# FMC_connectors.net
KiCad netlist of a schematic drawn in Altium Designer
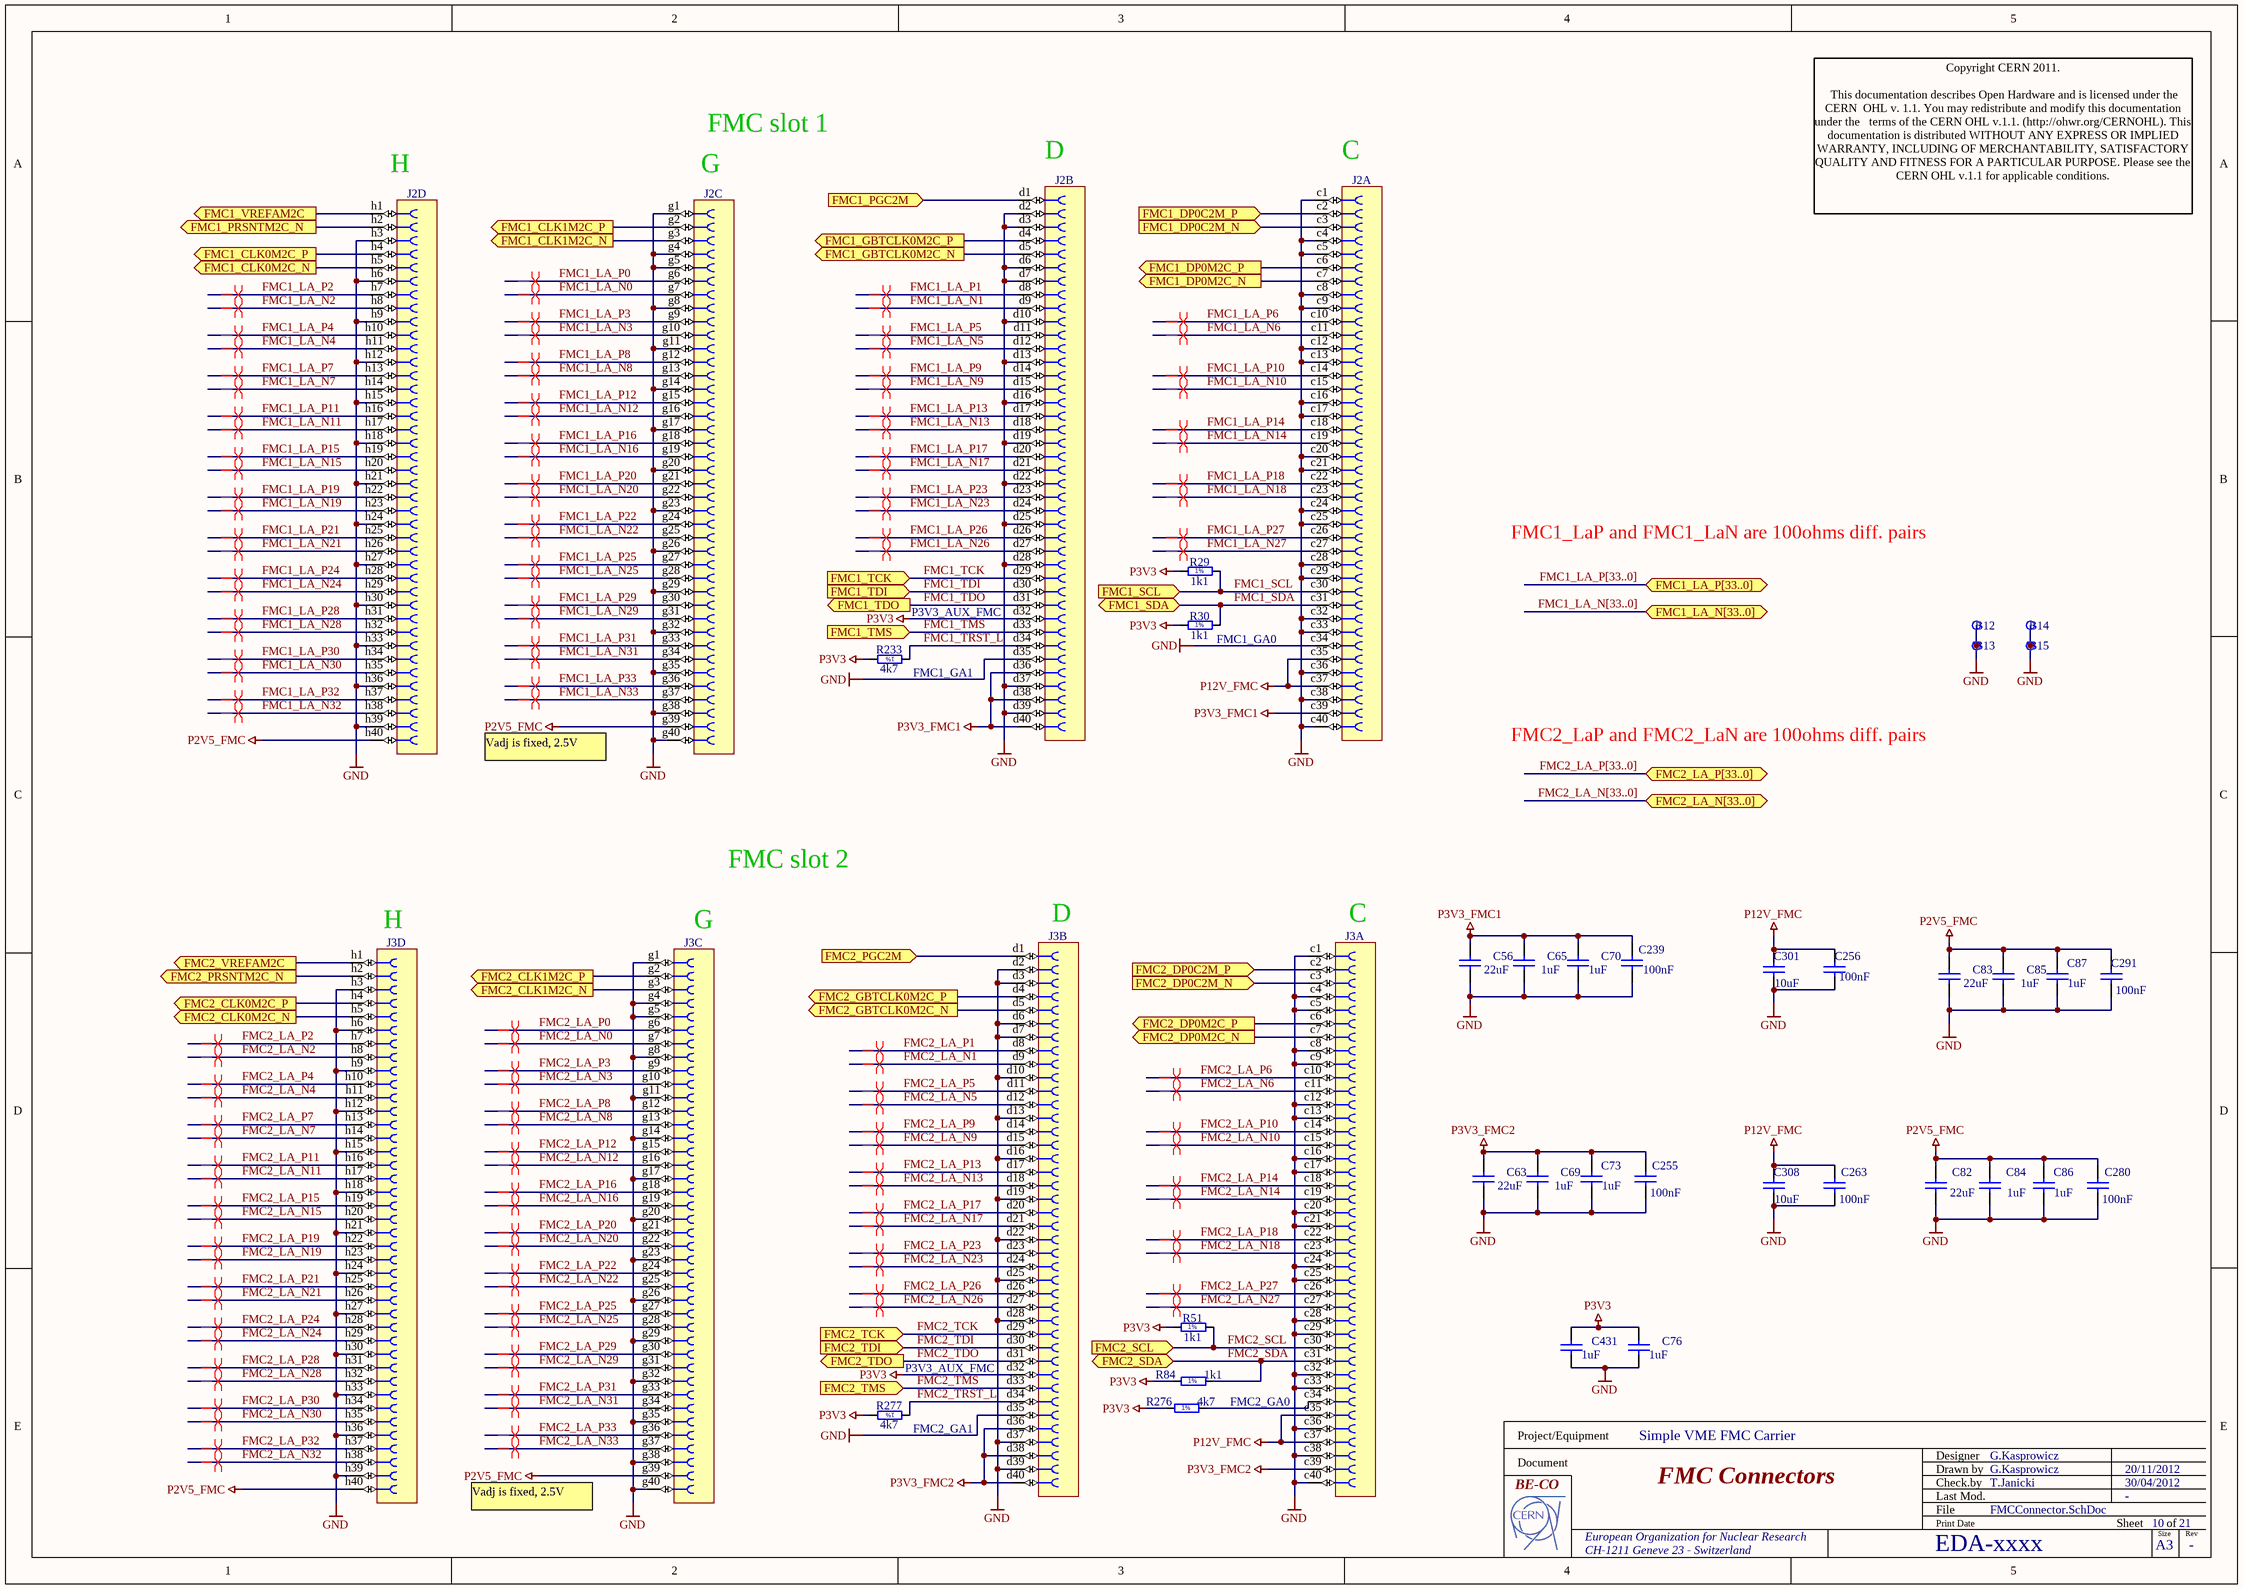
[diagram p0: FMC_connectors.SchDoc]

(export (version "E")
  (design (tool "Eeschema 10.0.6"))
  (components
    (comp (ref "B12")
      (value "Plated Hole")
      (footprint "MTG270_500")
      (description "Single Terminal Socket")
      (fields (field (name "PART NUMBER") "PLATED_HOLE2.7_PAD5.0") (field (name "AUTHOR") "CERN DEM JMW"))
      (libsource (lib "Eletro-mechanical") (part "Single Terminal Socket"))
    )
    (comp (ref "B13")
      (value "Plated Hole")
      (footprint "MTG270_500")
      (description "Single Terminal Socket")
      (fields (field (name "PART NUMBER") "PLATED_HOLE2.7_PAD5.0") (field (name "AUTHOR") "CERN DEM JMW"))
      (libsource (lib "Eletro-mechanical") (part "Single Terminal Socket"))
    )
    (comp (ref "B14")
      (value "Plated Hole")
      (footprint "MTG270_500")
      (description "Single Terminal Socket")
      (fields (field (name "PART NUMBER") "PLATED_HOLE2.7_PAD5.0") (field (name "AUTHOR") "CERN DEM JMW"))
      (libsource (lib "Eletro-mechanical") (part "Single Terminal Socket"))
    )
    (comp (ref "B15")
      (value "Plated Hole")
      (footprint "MTG270_500")
      (description "Single Terminal Socket")
      (fields (field (name "PART NUMBER") "PLATED_HOLE2.7_PAD5.0") (field (name "AUTHOR") "CERN DEM JMW"))
      (libsource (lib "Eletro-mechanical") (part "Single Terminal Socket"))
    )
    (comp (ref "C56")
      (value "22uF")
      (footprint "CAPC3216X180N")
      (description "Non-polarised capacitor")
      (fields
        (field (name "PART NUMBER") "CC1206_22UF_10V_10%_X7R")
        (field (name "VOLTAGE") "10V")
        (field (name "AUTHOR") "CERN DEM JLC")
      )
      (libsource (lib "Capacitors") (part "Capacitor - non polarized"))
    )
    (comp (ref "C63")
      (value "22uF")
      (footprint "CAPC3216X180N")
      (description "Non-polarised capacitor")
      (fields
        (field (name "PART NUMBER") "CC1206_22UF_10V_10%_X7R")
        (field (name "VOLTAGE") "10V")
        (field (name "AUTHOR") "CERN DEM JLC")
      )
      (libsource (lib "Capacitors") (part "Capacitor - non polarized"))
    )
    (comp (ref "C65")
      (value "1uF")
      (footprint "CAPC1608X87N")
      (description "Non-polarised capacitor")
      (fields
        (field (name "PART NUMBER") "CC0603_1UF_16V_10%_X7R")
        (field (name "VOLTAGE") "16V")
        (field (name "AUTHOR") "CERN DEM JLC")
      )
      (libsource (lib "Capacitors") (part "Capacitor - non polarized"))
    )
    (comp (ref "C69")
      (value "1uF")
      (footprint "CAPC1608X87N")
      (description "Non-polarised capacitor")
      (fields
        (field (name "PART NUMBER") "CC0603_1UF_16V_10%_X7R")
        (field (name "VOLTAGE") "16V")
        (field (name "AUTHOR") "CERN DEM JLC")
      )
      (libsource (lib "Capacitors") (part "Capacitor - non polarized"))
    )
    (comp (ref "C70")
      (value "1uF")
      (footprint "CAPC1608X87N")
      (description "Non-polarised capacitor")
      (fields
        (field (name "PART NUMBER") "CC0603_1UF_16V_10%_X7R")
        (field (name "VOLTAGE") "16V")
        (field (name "AUTHOR") "CERN DEM JLC")
      )
      (libsource (lib "Capacitors") (part "Capacitor - non polarized"))
    )
    (comp (ref "C73")
      (value "1uF")
      (footprint "CAPC1608X87N")
      (description "Non-polarised capacitor")
      (fields
        (field (name "PART NUMBER") "CC0603_1UF_16V_10%_X7R")
        (field (name "VOLTAGE") "16V")
        (field (name "AUTHOR") "CERN DEM JLC")
      )
      (libsource (lib "Capacitors") (part "Capacitor - non polarized"))
    )
    (comp (ref "C76")
      (value "1uF")
      (footprint "CAPC1608X87N")
      (description "Non-polarised capacitor")
      (fields
        (field (name "PART NUMBER") "CC0603_1UF_16V_10%_X7R")
        (field (name "VOLTAGE") "16V")
        (field (name "AUTHOR") "CERN DEM JLC")
      )
      (libsource (lib "Capacitors") (part "Capacitor - non polarized"))
    )
    (comp (ref "C82")
      (value "22uF")
      (footprint "CAPC3216X180N")
      (description "Non-polarised capacitor")
      (fields
        (field (name "PART NUMBER") "CC1206_22UF_10V_10%_X7R")
        (field (name "VOLTAGE") "10V")
        (field (name "AUTHOR") "CERN DEM JLC")
      )
      (libsource (lib "Capacitors") (part "Capacitor - non polarized"))
    )
    (comp (ref "C83")
      (value "22uF")
      (footprint "CAPC3216X180N")
      (description "Non-polarised capacitor")
      (fields
        (field (name "PART NUMBER") "CC1206_22UF_10V_10%_X7R")
        (field (name "VOLTAGE") "10V")
        (field (name "AUTHOR") "CERN DEM JLC")
      )
      (libsource (lib "Capacitors") (part "Capacitor - non polarized"))
    )
    (comp (ref "C84")
      (value "1uF")
      (footprint "CAPC1608X87N")
      (description "Non-polarised capacitor")
      (fields
        (field (name "PART NUMBER") "CC0603_1UF_16V_10%_X7R")
        (field (name "VOLTAGE") "16V")
        (field (name "AUTHOR") "CERN DEM JLC")
      )
      (libsource (lib "Capacitors") (part "Capacitor - non polarized"))
    )
    (comp (ref "C85")
      (value "1uF")
      (footprint "CAPC1608X87N")
      (description "Non-polarised capacitor")
      (fields
        (field (name "PART NUMBER") "CC0603_1UF_16V_10%_X7R")
        (field (name "VOLTAGE") "16V")
        (field (name "AUTHOR") "CERN DEM JLC")
      )
      (libsource (lib "Capacitors") (part "Capacitor - non polarized"))
    )
    (comp (ref "C86")
      (value "1uF")
      (footprint "CAPC1608X87N")
      (description "Non-polarised capacitor")
      (fields
        (field (name "PART NUMBER") "CC0603_1UF_16V_10%_X7R")
        (field (name "VOLTAGE") "16V")
        (field (name "AUTHOR") "CERN DEM JLC")
      )
      (libsource (lib "Capacitors") (part "Capacitor - non polarized"))
    )
    (comp (ref "C87")
      (value "1uF")
      (footprint "CAPC1608X87N")
      (description "Non-polarised capacitor")
      (fields
        (field (name "PART NUMBER") "CC0603_1UF_16V_10%_X7R")
        (field (name "VOLTAGE") "16V")
        (field (name "AUTHOR") "CERN DEM JLC")
      )
      (libsource (lib "Capacitors") (part "Capacitor - non polarized"))
    )
    (comp (ref "C239")
      (value "100nF")
      (footprint "CAPC1005X55N")
      (description "Non-polarised capacitor")
      (fields
        (field (name "PART NUMBER") "CC0402_100NF_16V_10%_X7R")
        (field (name "VOLTAGE") "16V")
        (field (name "AUTHOR") "CERN DEM JLC")
      )
      (libsource (lib "Capacitors") (part "Capacitor - non polarized"))
    )
    (comp (ref "C255")
      (value "100nF")
      (footprint "CAPC1005X55N")
      (description "Non-polarised capacitor")
      (fields
        (field (name "PART NUMBER") "CC0402_100NF_16V_10%_X7R")
        (field (name "VOLTAGE") "16V")
        (field (name "AUTHOR") "CERN DEM JLC")
      )
      (libsource (lib "Capacitors") (part "Capacitor - non polarized"))
    )
    (comp (ref "C256")
      (value "100nF")
      (footprint "CAPC1005X55N")
      (description "Non-polarised capacitor")
      (fields
        (field (name "PART NUMBER") "CC0402_100NF_16V_10%_X7R")
        (field (name "VOLTAGE") "16V")
        (field (name "AUTHOR") "CERN DEM JLC")
      )
      (libsource (lib "Capacitors") (part "Capacitor - non polarized"))
    )
    (comp (ref "C263")
      (value "100nF")
      (footprint "CAPC1005X55N")
      (description "Non-polarised capacitor")
      (fields
        (field (name "PART NUMBER") "CC0402_100NF_16V_10%_X7R")
        (field (name "VOLTAGE") "16V")
        (field (name "AUTHOR") "CERN DEM JLC")
      )
      (libsource (lib "Capacitors") (part "Capacitor - non polarized"))
    )
    (comp (ref "C280")
      (value "100nF")
      (footprint "CAPC1005X55N")
      (description "Non-polarised capacitor")
      (fields
        (field (name "PART NUMBER") "CC0402_100NF_16V_10%_X7R")
        (field (name "VOLTAGE") "16V")
        (field (name "AUTHOR") "CERN DEM JLC")
      )
      (libsource (lib "Capacitors") (part "Capacitor - non polarized"))
    )
    (comp (ref "C291")
      (value "100nF")
      (footprint "CAPC1005X55N")
      (description "Non-polarised capacitor")
      (fields
        (field (name "PART NUMBER") "CC0402_100NF_16V_10%_X7R")
        (field (name "VOLTAGE") "16V")
        (field (name "AUTHOR") "CERN DEM JLC")
      )
      (libsource (lib "Capacitors") (part "Capacitor - non polarized"))
    )
    (comp (ref "C301")
      (value "10uF")
      (footprint "CAPC3225X270N")
      (description "Non-polarised capacitor")
      (fields
        (field (name "PART NUMBER") "CC1210_10UF_25V_10%_X7R")
        (field (name "VOLTAGE") "25V")
        (field (name "AUTHOR") "CERN DEM JLC")
      )
      (libsource (lib "Capacitors") (part "Capacitor - non polarized"))
    )
    (comp (ref "C308")
      (value "10uF")
      (footprint "CAPC3225X270N")
      (description "Non-polarised capacitor")
      (fields
        (field (name "PART NUMBER") "CC1210_10UF_25V_10%_X7R")
        (field (name "VOLTAGE") "25V")
        (field (name "AUTHOR") "CERN DEM JLC")
      )
      (libsource (lib "Capacitors") (part "Capacitor - non polarized"))
    )
    (comp (ref "C431")
      (value "1uF")
      (footprint "CAPC1608X87N")
      (description "Non-polarised capacitor")
      (fields
        (field (name "PART NUMBER") "CC0603_1UF_16V_10%_X7R")
        (field (name "VOLTAGE") "16V")
        (field (name "AUTHOR") "CERN DEM JLC")
      )
      (libsource (lib "Capacitors") (part "Capacitor - non polarized"))
    )
    (comp (ref "J2")
      (value "VITA 57")
      (footprint "SAMTEC_ASP-134603-01")
      (description "Connector VITA 57, 160 Female contacts in 4 row cdgh")
      (fields
        (field (name "PART NUMBER") "SAMTEC_ASP-134603-01")
        (field (name "MANUFACTURER") "SAMTEC")
        (field (name "AUTHOR") "CERN DEM JLC")
      )
      (libsource (lib "Connectors") (part "Connector VITA 57 160 Female (cdgh)"))
    )
    (comp (ref "J3")
      (value "VITA 57")
      (footprint "SAMTEC_ASP-134603-01")
      (description "Connector VITA 57, 160 Female contacts in 4 row cdgh")
      (fields
        (field (name "PART NUMBER") "SAMTEC_ASP-134603-01")
        (field (name "MANUFACTURER") "SAMTEC")
        (field (name "AUTHOR") "CERN DEM JLC")
      )
      (libsource (lib "Connectors") (part "Connector VITA 57 160 Female (cdgh)"))
    )
    (comp (ref "R29")
      (value "1k1")
      (footprint "RESC1608X55N")
      (description "Resistor - 1%")
      (fields
        (field (name "PART NUMBER") "R0603_1K1_1%_0.1W_100PPM")
        (field (name "POWER") "0.1W")
        (field (name "AUTHOR") "CERN DEM JLC")
      )
      (libsource (lib "Resistors") (part "Resistor - 1%"))
    )
    (comp (ref "R30")
      (value "1k1")
      (footprint "RESC1608X55N")
      (description "Resistor - 1%")
      (fields
        (field (name "PART NUMBER") "R0603_1K1_1%_0.1W_100PPM")
        (field (name "POWER") "0.1W")
        (field (name "AUTHOR") "CERN DEM JLC")
      )
      (libsource (lib "Resistors") (part "Resistor - 1%"))
    )
    (comp (ref "R51")
      (value "1k1")
      (footprint "RESC1608X55N")
      (description "Resistor - 1%")
      (fields
        (field (name "PART NUMBER") "R0603_1K1_1%_0.1W_100PPM")
        (field (name "POWER") "0.1W")
        (field (name "AUTHOR") "CERN DEM JLC")
      )
      (libsource (lib "Resistors") (part "Resistor - 1%"))
    )
    (comp (ref "R84")
      (value "1k1")
      (footprint "RESC1608X55N")
      (description "Resistor - 1%")
      (fields
        (field (name "PART NUMBER") "R0603_1K1_1%_0.1W_100PPM")
        (field (name "POWER") "0.1W")
        (field (name "AUTHOR") "CERN DEM JLC")
      )
      (libsource (lib "Resistors") (part "Resistor - 1%"))
    )
    (comp (ref "R233")
      (value "4k7")
      (footprint "RESC1608X55N")
      (description "Resistor - 1%")
      (fields
        (field (name "PART NUMBER") "R0603_4K7_1%_0.1W_100PPM")
        (field (name "POWER") "0.1W")
        (field (name "AUTHOR") "CERN DEM JLC")
      )
      (libsource (lib "") (part "Resistor - 1%_1"))
    )
    (comp (ref "R276")
      (value "4k7")
      (footprint "RESC1608X55N")
      (description "Resistor - 1%")
      (fields
        (field (name "PART NUMBER") "R0603_4K7_1%_0.1W_100PPM")
        (field (name "POWER") "0.1W")
        (field (name "AUTHOR") "CERN DEM JLC")
      )
      (libsource (lib "Resistors") (part "Resistor - 1%"))
    )
    (comp (ref "R277")
      (value "4k7")
      (footprint "RESC1608X55N")
      (description "Resistor - 1%")
      (fields
        (field (name "PART NUMBER") "R0603_4K7_1%_0.1W_100PPM")
        (field (name "POWER") "0.1W")
        (field (name "AUTHOR") "CERN DEM JLC")
      )
      (libsource (lib "") (part "Resistor - 1%_1"))
    )
  )
  (nets
    (net (code "1") (name "/FMC1_CLK0M2C_N") (class "Default")
      (node (ref "J2") (pin "h5") (pinfunction "h5_h5") (pintype "bidirectional"))
    )
    (net (code "2") (name "/FMC1_CLK0M2C_P") (class "Default")
      (node (ref "J2") (pin "h4") (pinfunction "h4_h4") (pintype "bidirectional"))
    )
    (net (code "3") (name "/FMC1_CLK1M2C_N") (class "Default")
      (node (ref "J2") (pin "g3") (pinfunction "g3_g3") (pintype "bidirectional"))
    )
    (net (code "4") (name "/FMC1_CLK1M2C_P") (class "Default")
      (node (ref "J2") (pin "g2") (pinfunction "g2_g2") (pintype "bidirectional"))
    )
    (net (code "5") (name "/FMC1_DP0C2M_N") (class "Default")
      (node (ref "J2") (pin "c3") (pinfunction "c3_c3") (pintype "bidirectional"))
    )
    (net (code "6") (name "/FMC1_DP0C2M_P") (class "Default")
      (node (ref "J2") (pin "c2") (pinfunction "c2_c2") (pintype "bidirectional"))
    )
    (net (code "7") (name "/FMC1_DP0M2C_N") (class "Default")
      (node (ref "J2") (pin "c7") (pinfunction "c7_c7") (pintype "bidirectional"))
    )
    (net (code "8") (name "/FMC1_DP0M2C_P") (class "Default")
      (node (ref "J2") (pin "c6") (pinfunction "c6_c6") (pintype "bidirectional"))
    )
    (net (code "9") (name "/FMC1_GBTCLK0M2C_N") (class "Default")
      (node (ref "J2") (pin "d5") (pinfunction "d5_d5") (pintype "bidirectional"))
    )
    (net (code "10") (name "/FMC1_GBTCLK0M2C_P") (class "Default")
      (node (ref "J2") (pin "d4") (pinfunction "d4_d4") (pintype "bidirectional"))
    )
    (net (code "11") (name "/FMC1_LA_N0") (class "Default")
      (node (ref "J2") (pin "g7") (pinfunction "g7_g7") (pintype "bidirectional"))
    )
    (net (code "12") (name "/FMC1_LA_N1") (class "Default")
      (node (ref "J2") (pin "d9") (pinfunction "d9_d9") (pintype "bidirectional"))
    )
    (net (code "13") (name "/FMC1_LA_N2") (class "Default")
      (node (ref "J2") (pin "h8") (pinfunction "h8_h8") (pintype "bidirectional"))
    )
    (net (code "14") (name "/FMC1_LA_N3") (class "Default")
      (node (ref "J2") (pin "g10") (pinfunction "g10_g10") (pintype "bidirectional"))
    )
    (net (code "15") (name "/FMC1_LA_N4") (class "Default")
      (node (ref "J2") (pin "h11") (pinfunction "h11_h11") (pintype "bidirectional"))
    )
    (net (code "16") (name "/FMC1_LA_N5") (class "Default")
      (node (ref "J2") (pin "d12") (pinfunction "d12_d12") (pintype "bidirectional"))
    )
    (net (code "17") (name "/FMC1_LA_N6") (class "Default")
      (node (ref "J2") (pin "c11") (pinfunction "c11_c11") (pintype "bidirectional"))
    )
    (net (code "18") (name "/FMC1_LA_N7") (class "Default")
      (node (ref "J2") (pin "h14") (pinfunction "h14_h14") (pintype "bidirectional"))
    )
    (net (code "19") (name "/FMC1_LA_N8") (class "Default")
      (node (ref "J2") (pin "g13") (pinfunction "g13_g13") (pintype "bidirectional"))
    )
    (net (code "20") (name "/FMC1_LA_N9") (class "Default")
      (node (ref "J2") (pin "d15") (pinfunction "d15_d15") (pintype "bidirectional"))
    )
    (net (code "21") (name "/FMC1_LA_N10") (class "Default")
      (node (ref "J2") (pin "c15") (pinfunction "c15_c15") (pintype "bidirectional"))
    )
    (net (code "22") (name "/FMC1_LA_N11") (class "Default")
      (node (ref "J2") (pin "h17") (pinfunction "h17_h17") (pintype "bidirectional"))
    )
    (net (code "23") (name "/FMC1_LA_N12") (class "Default")
      (node (ref "J2") (pin "g16") (pinfunction "g16_g16") (pintype "bidirectional"))
    )
    (net (code "24") (name "/FMC1_LA_N13") (class "Default")
      (node (ref "J2") (pin "d18") (pinfunction "d18_d18") (pintype "bidirectional"))
    )
    (net (code "25") (name "/FMC1_LA_N14") (class "Default")
      (node (ref "J2") (pin "c19") (pinfunction "c19_c19") (pintype "bidirectional"))
    )
    (net (code "26") (name "/FMC1_LA_N15") (class "Default")
      (node (ref "J2") (pin "h20") (pinfunction "h20_h20") (pintype "bidirectional"))
    )
    (net (code "27") (name "/FMC1_LA_N16") (class "Default")
      (node (ref "J2") (pin "g19") (pinfunction "g19_g19") (pintype "bidirectional"))
    )
    (net (code "28") (name "/FMC1_LA_N17") (class "Default")
      (node (ref "J2") (pin "d21") (pinfunction "d21_d21") (pintype "bidirectional"))
    )
    (net (code "29") (name "/FMC1_LA_N18") (class "Default")
      (node (ref "J2") (pin "c23") (pinfunction "c23_c23") (pintype "bidirectional"))
    )
    (net (code "30") (name "/FMC1_LA_N19") (class "Default")
      (node (ref "J2") (pin "h23") (pinfunction "h23_h23") (pintype "bidirectional"))
    )
    (net (code "31") (name "/FMC1_LA_N20") (class "Default")
      (node (ref "J2") (pin "g22") (pinfunction "g22_g22") (pintype "bidirectional"))
    )
    (net (code "32") (name "/FMC1_LA_N21") (class "Default")
      (node (ref "J2") (pin "h26") (pinfunction "h26_h26") (pintype "bidirectional"))
    )
    (net (code "33") (name "/FMC1_LA_N22") (class "Default")
      (node (ref "J2") (pin "g25") (pinfunction "g25_g25") (pintype "bidirectional"))
    )
    (net (code "34") (name "/FMC1_LA_N23") (class "Default")
      (node (ref "J2") (pin "d24") (pinfunction "d24_d24") (pintype "bidirectional"))
    )
    (net (code "35") (name "/FMC1_LA_N24") (class "Default")
      (node (ref "J2") (pin "h29") (pinfunction "h29_h29") (pintype "bidirectional"))
    )
    (net (code "36") (name "/FMC1_LA_N25") (class "Default")
      (node (ref "J2") (pin "g28") (pinfunction "g28_g28") (pintype "bidirectional"))
    )
    (net (code "37") (name "/FMC1_LA_N26") (class "Default")
      (node (ref "J2") (pin "d27") (pinfunction "d27_d27") (pintype "bidirectional"))
    )
    (net (code "38") (name "/FMC1_LA_N27") (class "Default")
      (node (ref "J2") (pin "c27") (pinfunction "c27_c27") (pintype "bidirectional"))
    )
    (net (code "39") (name "/FMC1_LA_N28") (class "Default")
      (node (ref "J2") (pin "h32") (pinfunction "h32_h32") (pintype "bidirectional"))
    )
    (net (code "40") (name "/FMC1_LA_N29") (class "Default")
      (node (ref "J2") (pin "g31") (pinfunction "g31_g31") (pintype "bidirectional"))
    )
    (net (code "41") (name "/FMC1_LA_N30") (class "Default")
      (node (ref "J2") (pin "h35") (pinfunction "h35_h35") (pintype "bidirectional"))
    )
    (net (code "42") (name "/FMC1_LA_N31") (class "Default")
      (node (ref "J2") (pin "g34") (pinfunction "g34_g34") (pintype "bidirectional"))
    )
    (net (code "43") (name "/FMC1_LA_N32") (class "Default")
      (node (ref "J2") (pin "h38") (pinfunction "h38_h38") (pintype "bidirectional"))
    )
    (net (code "44") (name "/FMC1_LA_N33") (class "Default")
      (node (ref "J2") (pin "g37") (pinfunction "g37_g37") (pintype "bidirectional"))
    )
    (net (code "46") (name "/FMC1_LA_P0") (class "Default")
      (node (ref "J2") (pin "g6") (pinfunction "g6_g6") (pintype "bidirectional"))
    )
    (net (code "47") (name "/FMC1_LA_P1") (class "Default")
      (node (ref "J2") (pin "d8") (pinfunction "d8_d8") (pintype "bidirectional"))
    )
    (net (code "48") (name "/FMC1_LA_P2") (class "Default")
      (node (ref "J2") (pin "h7") (pinfunction "h7_h7") (pintype "bidirectional"))
    )
    (net (code "49") (name "/FMC1_LA_P3") (class "Default")
      (node (ref "J2") (pin "g9") (pinfunction "g9_g9") (pintype "bidirectional"))
    )
    (net (code "50") (name "/FMC1_LA_P4") (class "Default")
      (node (ref "J2") (pin "h10") (pinfunction "h10_h10") (pintype "bidirectional"))
    )
    (net (code "51") (name "/FMC1_LA_P5") (class "Default")
      (node (ref "J2") (pin "d11") (pinfunction "d11_d11") (pintype "bidirectional"))
    )
    (net (code "52") (name "/FMC1_LA_P6") (class "Default")
      (node (ref "J2") (pin "c10") (pinfunction "c10_c10") (pintype "bidirectional"))
    )
    (net (code "53") (name "/FMC1_LA_P7") (class "Default")
      (node (ref "J2") (pin "h13") (pinfunction "h13_h13") (pintype "bidirectional"))
    )
    (net (code "54") (name "/FMC1_LA_P8") (class "Default")
      (node (ref "J2") (pin "g12") (pinfunction "g12_g12") (pintype "bidirectional"))
    )
    (net (code "55") (name "/FMC1_LA_P9") (class "Default")
      (node (ref "J2") (pin "d14") (pinfunction "d14_d14") (pintype "bidirectional"))
    )
    (net (code "56") (name "/FMC1_LA_P10") (class "Default")
      (node (ref "J2") (pin "c14") (pinfunction "c14_c14") (pintype "bidirectional"))
    )
    (net (code "57") (name "/FMC1_LA_P11") (class "Default")
      (node (ref "J2") (pin "h16") (pinfunction "h16_h16") (pintype "bidirectional"))
    )
    (net (code "58") (name "/FMC1_LA_P12") (class "Default")
      (node (ref "J2") (pin "g15") (pinfunction "g15_g15") (pintype "bidirectional"))
    )
    (net (code "59") (name "/FMC1_LA_P13") (class "Default")
      (node (ref "J2") (pin "d17") (pinfunction "d17_d17") (pintype "bidirectional"))
    )
    (net (code "60") (name "/FMC1_LA_P14") (class "Default")
      (node (ref "J2") (pin "c18") (pinfunction "c18_c18") (pintype "bidirectional"))
    )
    (net (code "61") (name "/FMC1_LA_P15") (class "Default")
      (node (ref "J2") (pin "h19") (pinfunction "h19_h19") (pintype "bidirectional"))
    )
    (net (code "62") (name "/FMC1_LA_P16") (class "Default")
      (node (ref "J2") (pin "g18") (pinfunction "g18_g18") (pintype "bidirectional"))
    )
    (net (code "63") (name "/FMC1_LA_P17") (class "Default")
      (node (ref "J2") (pin "d20") (pinfunction "d20_d20") (pintype "bidirectional"))
    )
    (net (code "64") (name "/FMC1_LA_P18") (class "Default")
      (node (ref "J2") (pin "c22") (pinfunction "c22_c22") (pintype "bidirectional"))
    )
    (net (code "65") (name "/FMC1_LA_P19") (class "Default")
      (node (ref "J2") (pin "h22") (pinfunction "h22_h22") (pintype "bidirectional"))
    )
    (net (code "66") (name "/FMC1_LA_P20") (class "Default")
      (node (ref "J2") (pin "g21") (pinfunction "g21_g21") (pintype "bidirectional"))
    )
    (net (code "67") (name "/FMC1_LA_P21") (class "Default")
      (node (ref "J2") (pin "h25") (pinfunction "h25_h25") (pintype "bidirectional"))
    )
    (net (code "68") (name "/FMC1_LA_P22") (class "Default")
      (node (ref "J2") (pin "g24") (pinfunction "g24_g24") (pintype "bidirectional"))
    )
    (net (code "69") (name "/FMC1_LA_P23") (class "Default")
      (node (ref "J2") (pin "d23") (pinfunction "d23_d23") (pintype "bidirectional"))
    )
    (net (code "70") (name "/FMC1_LA_P24") (class "Default")
      (node (ref "J2") (pin "h28") (pinfunction "h28_h28") (pintype "bidirectional"))
    )
    (net (code "71") (name "/FMC1_LA_P25") (class "Default")
      (node (ref "J2") (pin "g27") (pinfunction "g27_g27") (pintype "bidirectional"))
    )
    (net (code "72") (name "/FMC1_LA_P26") (class "Default")
      (node (ref "J2") (pin "d26") (pinfunction "d26_d26") (pintype "bidirectional"))
    )
    (net (code "73") (name "/FMC1_LA_P27") (class "Default")
      (node (ref "J2") (pin "c26") (pinfunction "c26_c26") (pintype "bidirectional"))
    )
    (net (code "74") (name "/FMC1_LA_P28") (class "Default")
      (node (ref "J2") (pin "h31") (pinfunction "h31_h31") (pintype "bidirectional"))
    )
    (net (code "75") (name "/FMC1_LA_P29") (class "Default")
      (node (ref "J2") (pin "g30") (pinfunction "g30_g30") (pintype "bidirectional"))
    )
    (net (code "76") (name "/FMC1_LA_P30") (class "Default")
      (node (ref "J2") (pin "h34") (pinfunction "h34_h34") (pintype "bidirectional"))
    )
    (net (code "77") (name "/FMC1_LA_P31") (class "Default")
      (node (ref "J2") (pin "g33") (pinfunction "g33_g33") (pintype "bidirectional"))
    )
    (net (code "78") (name "/FMC1_LA_P32") (class "Default")
      (node (ref "J2") (pin "h37") (pinfunction "h37_h37") (pintype "bidirectional"))
    )
    (net (code "79") (name "/FMC1_LA_P33") (class "Default")
      (node (ref "J2") (pin "g36") (pinfunction "g36_g36") (pintype "bidirectional"))
    )
    (net (code "81") (name "/FMC1_PGC2M") (class "Default")
      (node (ref "J2") (pin "d1") (pinfunction "d1_d1") (pintype "bidirectional"))
    )
    (net (code "82") (name "/FMC1_PRSNTM2C_N") (class "Default")
      (node (ref "J2") (pin "h2") (pinfunction "h2_h2") (pintype "bidirectional"))
    )
    (net (code "83") (name "/FMC1_SCL") (class "Default")
      (node (ref "J2") (pin "c30") (pinfunction "c30_c30") (pintype "bidirectional"))
      (node (ref "R29") (pin "2") (pinfunction "2_2") (pintype "passive"))
    )
    (net (code "84") (name "/FMC1_SDA") (class "Default")
      (node (ref "J2") (pin "c31") (pinfunction "c31_c31") (pintype "bidirectional"))
      (node (ref "R30") (pin "2") (pinfunction "2_2") (pintype "passive"))
    )
    (net (code "85") (name "/FMC1_TCK") (class "Default")
      (node (ref "J2") (pin "d29") (pinfunction "d29_d29") (pintype "bidirectional"))
    )
    (net (code "86") (name "/FMC1_TDI") (class "Default")
      (node (ref "J2") (pin "d30") (pinfunction "d30_d30") (pintype "bidirectional"))
    )
    (net (code "87") (name "/FMC1_TDO") (class "Default")
      (node (ref "J2") (pin "d31") (pinfunction "d31_d31") (pintype "bidirectional"))
    )
    (net (code "88") (name "/FMC1_TMS") (class "Default")
      (node (ref "J2") (pin "d33") (pinfunction "d33_d33") (pintype "bidirectional"))
    )
    (net (code "89") (name "/FMC1_TRST_L") (class "Default")
      (node (ref "J2") (pin "d34") (pinfunction "d34_d34") (pintype "bidirectional"))
      (node (ref "R233") (pin "1") (pinfunction "1_1") (pintype "passive"))
    )
    (net (code "90") (name "/FMC1_VREFAM2C") (class "Default")
      (node (ref "J2") (pin "h1") (pinfunction "h1_h1") (pintype "bidirectional"))
    )
    (net (code "91") (name "/FMC2_CLK0M2C_N") (class "Default")
      (node (ref "J3") (pin "h5") (pinfunction "h5_h5") (pintype "bidirectional"))
    )
    (net (code "92") (name "/FMC2_CLK0M2C_P") (class "Default")
      (node (ref "J3") (pin "h4") (pinfunction "h4_h4") (pintype "bidirectional"))
    )
    (net (code "93") (name "/FMC2_CLK1M2C_N") (class "Default")
      (node (ref "J3") (pin "g3") (pinfunction "g3_g3") (pintype "bidirectional"))
    )
    (net (code "94") (name "/FMC2_CLK1M2C_P") (class "Default")
      (node (ref "J3") (pin "g2") (pinfunction "g2_g2") (pintype "bidirectional"))
    )
    (net (code "95") (name "/FMC2_DP0C2M_N") (class "Default")
      (node (ref "J3") (pin "c3") (pinfunction "c3_c3") (pintype "bidirectional"))
    )
    (net (code "96") (name "/FMC2_DP0C2M_P") (class "Default")
      (node (ref "J3") (pin "c2") (pinfunction "c2_c2") (pintype "bidirectional"))
    )
    (net (code "97") (name "/FMC2_DP0M2C_N") (class "Default")
      (node (ref "J3") (pin "c7") (pinfunction "c7_c7") (pintype "bidirectional"))
    )
    (net (code "98") (name "/FMC2_DP0M2C_P") (class "Default")
      (node (ref "J3") (pin "c6") (pinfunction "c6_c6") (pintype "bidirectional"))
    )
    (net (code "99") (name "/FMC2_GBTCLK0M2C_N") (class "Default")
      (node (ref "J3") (pin "d5") (pinfunction "d5_d5") (pintype "bidirectional"))
    )
    (net (code "100") (name "/FMC2_GBTCLK0M2C_P") (class "Default")
      (node (ref "J3") (pin "d4") (pinfunction "d4_d4") (pintype "bidirectional"))
    )
    (net (code "101") (name "/FMC2_LA_N0") (class "Default")
      (node (ref "J3") (pin "g7") (pinfunction "g7_g7") (pintype "bidirectional"))
    )
    (net (code "102") (name "/FMC2_LA_N1") (class "Default")
      (node (ref "J3") (pin "d9") (pinfunction "d9_d9") (pintype "bidirectional"))
    )
    (net (code "103") (name "/FMC2_LA_N2") (class "Default")
      (node (ref "J3") (pin "h8") (pinfunction "h8_h8") (pintype "bidirectional"))
    )
    (net (code "104") (name "/FMC2_LA_N3") (class "Default")
      (node (ref "J3") (pin "g10") (pinfunction "g10_g10") (pintype "bidirectional"))
    )
    (net (code "105") (name "/FMC2_LA_N4") (class "Default")
      (node (ref "J3") (pin "h11") (pinfunction "h11_h11") (pintype "bidirectional"))
    )
    (net (code "106") (name "/FMC2_LA_N5") (class "Default")
      (node (ref "J3") (pin "d12") (pinfunction "d12_d12") (pintype "bidirectional"))
    )
    (net (code "107") (name "/FMC2_LA_N6") (class "Default")
      (node (ref "J3") (pin "c11") (pinfunction "c11_c11") (pintype "bidirectional"))
    )
    (net (code "108") (name "/FMC2_LA_N7") (class "Default")
      (node (ref "J3") (pin "h14") (pinfunction "h14_h14") (pintype "bidirectional"))
    )
    (net (code "109") (name "/FMC2_LA_N8") (class "Default")
      (node (ref "J3") (pin "g13") (pinfunction "g13_g13") (pintype "bidirectional"))
    )
    (net (code "110") (name "/FMC2_LA_N9") (class "Default")
      (node (ref "J3") (pin "d15") (pinfunction "d15_d15") (pintype "bidirectional"))
    )
    (net (code "111") (name "/FMC2_LA_N10") (class "Default")
      (node (ref "J3") (pin "c15") (pinfunction "c15_c15") (pintype "bidirectional"))
    )
    (net (code "112") (name "/FMC2_LA_N11") (class "Default")
      (node (ref "J3") (pin "h17") (pinfunction "h17_h17") (pintype "bidirectional"))
    )
    (net (code "113") (name "/FMC2_LA_N12") (class "Default")
      (node (ref "J3") (pin "g16") (pinfunction "g16_g16") (pintype "bidirectional"))
    )
    (net (code "114") (name "/FMC2_LA_N13") (class "Default")
      (node (ref "J3") (pin "d18") (pinfunction "d18_d18") (pintype "bidirectional"))
    )
    (net (code "115") (name "/FMC2_LA_N14") (class "Default")
      (node (ref "J3") (pin "c19") (pinfunction "c19_c19") (pintype "bidirectional"))
    )
    (net (code "116") (name "/FMC2_LA_N15") (class "Default")
      (node (ref "J3") (pin "h20") (pinfunction "h20_h20") (pintype "bidirectional"))
    )
    (net (code "117") (name "/FMC2_LA_N16") (class "Default")
      (node (ref "J3") (pin "g19") (pinfunction "g19_g19") (pintype "bidirectional"))
    )
    (net (code "118") (name "/FMC2_LA_N17") (class "Default")
      (node (ref "J3") (pin "d21") (pinfunction "d21_d21") (pintype "bidirectional"))
    )
    (net (code "119") (name "/FMC2_LA_N18") (class "Default")
      (node (ref "J3") (pin "c23") (pinfunction "c23_c23") (pintype "bidirectional"))
    )
    (net (code "120") (name "/FMC2_LA_N19") (class "Default")
      (node (ref "J3") (pin "h23") (pinfunction "h23_h23") (pintype "bidirectional"))
    )
    (net (code "121") (name "/FMC2_LA_N20") (class "Default")
      (node (ref "J3") (pin "g22") (pinfunction "g22_g22") (pintype "bidirectional"))
    )
    (net (code "122") (name "/FMC2_LA_N21") (class "Default")
      (node (ref "J3") (pin "h26") (pinfunction "h26_h26") (pintype "bidirectional"))
    )
    (net (code "123") (name "/FMC2_LA_N22") (class "Default")
      (node (ref "J3") (pin "g25") (pinfunction "g25_g25") (pintype "bidirectional"))
    )
    (net (code "124") (name "/FMC2_LA_N23") (class "Default")
      (node (ref "J3") (pin "d24") (pinfunction "d24_d24") (pintype "bidirectional"))
    )
    (net (code "125") (name "/FMC2_LA_N24") (class "Default")
      (node (ref "J3") (pin "h29") (pinfunction "h29_h29") (pintype "bidirectional"))
    )
    (net (code "126") (name "/FMC2_LA_N25") (class "Default")
      (node (ref "J3") (pin "g28") (pinfunction "g28_g28") (pintype "bidirectional"))
    )
    (net (code "127") (name "/FMC2_LA_N26") (class "Default")
      (node (ref "J3") (pin "d27") (pinfunction "d27_d27") (pintype "bidirectional"))
    )
    (net (code "128") (name "/FMC2_LA_N27") (class "Default")
      (node (ref "J3") (pin "c27") (pinfunction "c27_c27") (pintype "bidirectional"))
    )
    (net (code "129") (name "/FMC2_LA_N28") (class "Default")
      (node (ref "J3") (pin "h32") (pinfunction "h32_h32") (pintype "bidirectional"))
    )
    (net (code "130") (name "/FMC2_LA_N29") (class "Default")
      (node (ref "J3") (pin "g31") (pinfunction "g31_g31") (pintype "bidirectional"))
    )
    (net (code "131") (name "/FMC2_LA_N30") (class "Default")
      (node (ref "J3") (pin "h35") (pinfunction "h35_h35") (pintype "bidirectional"))
    )
    (net (code "132") (name "/FMC2_LA_N31") (class "Default")
      (node (ref "J3") (pin "g34") (pinfunction "g34_g34") (pintype "bidirectional"))
    )
    (net (code "133") (name "/FMC2_LA_N32") (class "Default")
      (node (ref "J3") (pin "h38") (pinfunction "h38_h38") (pintype "bidirectional"))
    )
    (net (code "134") (name "/FMC2_LA_N33") (class "Default")
      (node (ref "J3") (pin "g37") (pinfunction "g37_g37") (pintype "bidirectional"))
    )
    (net (code "136") (name "/FMC2_LA_P0") (class "Default")
      (node (ref "J3") (pin "g6") (pinfunction "g6_g6") (pintype "bidirectional"))
    )
    (net (code "137") (name "/FMC2_LA_P1") (class "Default")
      (node (ref "J3") (pin "d8") (pinfunction "d8_d8") (pintype "bidirectional"))
    )
    (net (code "138") (name "/FMC2_LA_P2") (class "Default")
      (node (ref "J3") (pin "h7") (pinfunction "h7_h7") (pintype "bidirectional"))
    )
    (net (code "139") (name "/FMC2_LA_P3") (class "Default")
      (node (ref "J3") (pin "g9") (pinfunction "g9_g9") (pintype "bidirectional"))
    )
    (net (code "140") (name "/FMC2_LA_P4") (class "Default")
      (node (ref "J3") (pin "h10") (pinfunction "h10_h10") (pintype "bidirectional"))
    )
    (net (code "141") (name "/FMC2_LA_P5") (class "Default")
      (node (ref "J3") (pin "d11") (pinfunction "d11_d11") (pintype "bidirectional"))
    )
    (net (code "142") (name "/FMC2_LA_P6") (class "Default")
      (node (ref "J3") (pin "c10") (pinfunction "c10_c10") (pintype "bidirectional"))
    )
    (net (code "143") (name "/FMC2_LA_P7") (class "Default")
      (node (ref "J3") (pin "h13") (pinfunction "h13_h13") (pintype "bidirectional"))
    )
    (net (code "144") (name "/FMC2_LA_P8") (class "Default")
      (node (ref "J3") (pin "g12") (pinfunction "g12_g12") (pintype "bidirectional"))
    )
    (net (code "145") (name "/FMC2_LA_P9") (class "Default")
      (node (ref "J3") (pin "d14") (pinfunction "d14_d14") (pintype "bidirectional"))
    )
    (net (code "146") (name "/FMC2_LA_P10") (class "Default")
      (node (ref "J3") (pin "c14") (pinfunction "c14_c14") (pintype "bidirectional"))
    )
    (net (code "147") (name "/FMC2_LA_P11") (class "Default")
      (node (ref "J3") (pin "h16") (pinfunction "h16_h16") (pintype "bidirectional"))
    )
    (net (code "148") (name "/FMC2_LA_P12") (class "Default")
      (node (ref "J3") (pin "g15") (pinfunction "g15_g15") (pintype "bidirectional"))
    )
    (net (code "149") (name "/FMC2_LA_P13") (class "Default")
      (node (ref "J3") (pin "d17") (pinfunction "d17_d17") (pintype "bidirectional"))
    )
    (net (code "150") (name "/FMC2_LA_P14") (class "Default")
      (node (ref "J3") (pin "c18") (pinfunction "c18_c18") (pintype "bidirectional"))
    )
    (net (code "151") (name "/FMC2_LA_P15") (class "Default")
      (node (ref "J3") (pin "h19") (pinfunction "h19_h19") (pintype "bidirectional"))
    )
    (net (code "152") (name "/FMC2_LA_P16") (class "Default")
      (node (ref "J3") (pin "g18") (pinfunction "g18_g18") (pintype "bidirectional"))
    )
    (net (code "153") (name "/FMC2_LA_P17") (class "Default")
      (node (ref "J3") (pin "d20") (pinfunction "d20_d20") (pintype "bidirectional"))
    )
    (net (code "154") (name "/FMC2_LA_P18") (class "Default")
      (node (ref "J3") (pin "c22") (pinfunction "c22_c22") (pintype "bidirectional"))
    )
    (net (code "155") (name "/FMC2_LA_P19") (class "Default")
      (node (ref "J3") (pin "h22") (pinfunction "h22_h22") (pintype "bidirectional"))
    )
    (net (code "156") (name "/FMC2_LA_P20") (class "Default")
      (node (ref "J3") (pin "g21") (pinfunction "g21_g21") (pintype "bidirectional"))
    )
    (net (code "157") (name "/FMC2_LA_P21") (class "Default")
      (node (ref "J3") (pin "h25") (pinfunction "h25_h25") (pintype "bidirectional"))
    )
    (net (code "158") (name "/FMC2_LA_P22") (class "Default")
      (node (ref "J3") (pin "g24") (pinfunction "g24_g24") (pintype "bidirectional"))
    )
    (net (code "159") (name "/FMC2_LA_P23") (class "Default")
      (node (ref "J3") (pin "d23") (pinfunction "d23_d23") (pintype "bidirectional"))
    )
    (net (code "160") (name "/FMC2_LA_P24") (class "Default")
      (node (ref "J3") (pin "h28") (pinfunction "h28_h28") (pintype "bidirectional"))
    )
    (net (code "161") (name "/FMC2_LA_P25") (class "Default")
      (node (ref "J3") (pin "g27") (pinfunction "g27_g27") (pintype "bidirectional"))
    )
    (net (code "162") (name "/FMC2_LA_P26") (class "Default")
      (node (ref "J3") (pin "d26") (pinfunction "d26_d26") (pintype "bidirectional"))
    )
    (net (code "163") (name "/FMC2_LA_P27") (class "Default")
      (node (ref "J3") (pin "c26") (pinfunction "c26_c26") (pintype "bidirectional"))
    )
    (net (code "164") (name "/FMC2_LA_P28") (class "Default")
      (node (ref "J3") (pin "h31") (pinfunction "h31_h31") (pintype "bidirectional"))
    )
    (net (code "165") (name "/FMC2_LA_P29") (class "Default")
      (node (ref "J3") (pin "g30") (pinfunction "g30_g30") (pintype "bidirectional"))
    )
    (net (code "166") (name "/FMC2_LA_P30") (class "Default")
      (node (ref "J3") (pin "h34") (pinfunction "h34_h34") (pintype "bidirectional"))
    )
    (net (code "167") (name "/FMC2_LA_P31") (class "Default")
      (node (ref "J3") (pin "g33") (pinfunction "g33_g33") (pintype "bidirectional"))
    )
    (net (code "168") (name "/FMC2_LA_P32") (class "Default")
      (node (ref "J3") (pin "h37") (pinfunction "h37_h37") (pintype "bidirectional"))
    )
    (net (code "169") (name "/FMC2_LA_P33") (class "Default")
      (node (ref "J3") (pin "g36") (pinfunction "g36_g36") (pintype "bidirectional"))
    )
    (net (code "171") (name "/FMC2_PGC2M") (class "Default")
      (node (ref "J3") (pin "d1") (pinfunction "d1_d1") (pintype "bidirectional"))
    )
    (net (code "172") (name "/FMC2_PRSNTM2C_N") (class "Default")
      (node (ref "J3") (pin "h2") (pinfunction "h2_h2") (pintype "bidirectional"))
    )
    (net (code "173") (name "/FMC2_SCL") (class "Default")
      (node (ref "J3") (pin "c30") (pinfunction "c30_c30") (pintype "bidirectional"))
      (node (ref "R51") (pin "2") (pinfunction "2_2") (pintype "passive"))
    )
    (net (code "174") (name "/FMC2_SDA") (class "Default")
      (node (ref "J3") (pin "c31") (pinfunction "c31_c31") (pintype "bidirectional"))
      (node (ref "R84") (pin "2") (pinfunction "2_2") (pintype "passive"))
    )
    (net (code "175") (name "/FMC2_TCK") (class "Default")
      (node (ref "J3") (pin "d29") (pinfunction "d29_d29") (pintype "bidirectional"))
    )
    (net (code "176") (name "/FMC2_TDI") (class "Default")
      (node (ref "J3") (pin "d30") (pinfunction "d30_d30") (pintype "bidirectional"))
    )
    (net (code "177") (name "/FMC2_TDO") (class "Default")
      (node (ref "J3") (pin "d31") (pinfunction "d31_d31") (pintype "bidirectional"))
    )
    (net (code "178") (name "/FMC2_TMS") (class "Default")
      (node (ref "J3") (pin "d33") (pinfunction "d33_d33") (pintype "bidirectional"))
    )
    (net (code "179") (name "/FMC2_TRST_L") (class "Default")
      (node (ref "J3") (pin "d34") (pinfunction "d34_d34") (pintype "bidirectional"))
      (node (ref "R277") (pin "1") (pinfunction "1_1") (pintype "passive"))
    )
    (net (code "180") (name "/FMC2_VREFAM2C") (class "Default")
      (node (ref "J3") (pin "h1") (pinfunction "h1_h1") (pintype "bidirectional"))
    )
    (net (code "181") (name "GND") (class "Default")
      (node (ref "B12") (pin "1") (pinfunction "1_1") (pintype "bidirectional"))
      (node (ref "B13") (pin "1") (pinfunction "1_1") (pintype "bidirectional"))
      (node (ref "B14") (pin "1") (pinfunction "1_1") (pintype "bidirectional"))
      (node (ref "B15") (pin "1") (pinfunction "1_1") (pintype "bidirectional"))
      (node (ref "C239") (pin "1") (pinfunction "1_1") (pintype "passive"))
      (node (ref "C255") (pin "1") (pinfunction "1_1") (pintype "passive"))
      (node (ref "C256") (pin "1") (pinfunction "1_1") (pintype "passive"))
      (node (ref "C263") (pin "1") (pinfunction "1_1") (pintype "passive"))
      (node (ref "C280") (pin "1") (pinfunction "1_1") (pintype "passive"))
      (node (ref "C291") (pin "1") (pinfunction "1_1") (pintype "passive"))
      (node (ref "C301") (pin "2") (pinfunction "2_2") (pintype "passive"))
      (node (ref "C308") (pin "2") (pinfunction "2_2") (pintype "passive"))
      (node (ref "C431") (pin "1") (pinfunction "1_1") (pintype "passive"))
      (node (ref "C56") (pin "1") (pinfunction "1_1") (pintype "passive"))
      (node (ref "C63") (pin "1") (pinfunction "1_1") (pintype "passive"))
      (node (ref "C65") (pin "1") (pinfunction "1_1") (pintype "passive"))
      (node (ref "C69") (pin "1") (pinfunction "1_1") (pintype "passive"))
      (node (ref "C70") (pin "1") (pinfunction "1_1") (pintype "passive"))
      (node (ref "C73") (pin "1") (pinfunction "1_1") (pintype "passive"))
      (node (ref "C76") (pin "1") (pinfunction "1_1") (pintype "passive"))
      (node (ref "C82") (pin "1") (pinfunction "1_1") (pintype "passive"))
      (node (ref "C83") (pin "1") (pinfunction "1_1") (pintype "passive"))
      (node (ref "C84") (pin "1") (pinfunction "1_1") (pintype "passive"))
      (node (ref "C85") (pin "1") (pinfunction "1_1") (pintype "passive"))
      (node (ref "C86") (pin "1") (pinfunction "1_1") (pintype "passive"))
      (node (ref "C87") (pin "1") (pinfunction "1_1") (pintype "passive"))
      (node (ref "J2") (pin "c1") (pinfunction "c1_c1") (pintype "bidirectional"))
      (node (ref "J2") (pin "c12") (pinfunction "c12_c12") (pintype "bidirectional"))
      (node (ref "J2") (pin "c13") (pinfunction "c13_c13") (pintype "bidirectional"))
      (node (ref "J2") (pin "c16") (pinfunction "c16_c16") (pintype "bidirectional"))
      (node (ref "J2") (pin "c17") (pinfunction "c17_c17") (pintype "bidirectional"))
      (node (ref "J2") (pin "c20") (pinfunction "c20_c20") (pintype "bidirectional"))
      (node (ref "J2") (pin "c21") (pinfunction "c21_c21") (pintype "bidirectional"))
      (node (ref "J2") (pin "c24") (pinfunction "c24_c24") (pintype "bidirectional"))
      (node (ref "J2") (pin "c25") (pinfunction "c25_c25") (pintype "bidirectional"))
      (node (ref "J2") (pin "c28") (pinfunction "c28_c28") (pintype "bidirectional"))
      (node (ref "J2") (pin "c29") (pinfunction "c29_c29") (pintype "bidirectional"))
      (node (ref "J2") (pin "c32") (pinfunction "c32_c32") (pintype "bidirectional"))
      (node (ref "J2") (pin "c33") (pinfunction "c33_c33") (pintype "bidirectional"))
      (node (ref "J2") (pin "c34") (pinfunction "c34_c34") (pintype "bidirectional"))
      (node (ref "J2") (pin "c36") (pinfunction "c36_c36") (pintype "bidirectional"))
      (node (ref "J2") (pin "c38") (pinfunction "c38_c38") (pintype "bidirectional"))
      (node (ref "J2") (pin "c4") (pinfunction "c4_c4") (pintype "bidirectional"))
      (node (ref "J2") (pin "c40") (pinfunction "c40_c40") (pintype "bidirectional"))
      (node (ref "J2") (pin "c5") (pinfunction "c5_c5") (pintype "bidirectional"))
      (node (ref "J2") (pin "c8") (pinfunction "c8_c8") (pintype "bidirectional"))
      (node (ref "J2") (pin "c9") (pinfunction "c9_c9") (pintype "bidirectional"))
      (node (ref "J2") (pin "d10") (pinfunction "d10_d10") (pintype "bidirectional"))
      (node (ref "J2") (pin "d13") (pinfunction "d13_d13") (pintype "bidirectional"))
      (node (ref "J2") (pin "d16") (pinfunction "d16_d16") (pintype "bidirectional"))
      (node (ref "J2") (pin "d19") (pinfunction "d19_d19") (pintype "bidirectional"))
      (node (ref "J2") (pin "d2") (pinfunction "d2_d2") (pintype "bidirectional"))
      (node (ref "J2") (pin "d22") (pinfunction "d22_d22") (pintype "bidirectional"))
      (node (ref "J2") (pin "d25") (pinfunction "d25_d25") (pintype "bidirectional"))
      (node (ref "J2") (pin "d28") (pinfunction "d28_d28") (pintype "bidirectional"))
      (node (ref "J2") (pin "d3") (pinfunction "d3_d3") (pintype "bidirectional"))
      (node (ref "J2") (pin "d35") (pinfunction "d35_d35") (pintype "bidirectional"))
      (node (ref "J2") (pin "d37") (pinfunction "d37_d37") (pintype "bidirectional"))
      (node (ref "J2") (pin "d39") (pinfunction "d39_d39") (pintype "bidirectional"))
      (node (ref "J2") (pin "d6") (pinfunction "d6_d6") (pintype "bidirectional"))
      (node (ref "J2") (pin "d7") (pinfunction "d7_d7") (pintype "bidirectional"))
      (node (ref "J2") (pin "g1") (pinfunction "g1_g1") (pintype "bidirectional"))
      (node (ref "J2") (pin "g11") (pinfunction "g11_g11") (pintype "bidirectional"))
      (node (ref "J2") (pin "g14") (pinfunction "g14_g14") (pintype "bidirectional"))
      (node (ref "J2") (pin "g17") (pinfunction "g17_g17") (pintype "bidirectional"))
      (node (ref "J2") (pin "g20") (pinfunction "g20_g20") (pintype "bidirectional"))
      (node (ref "J2") (pin "g23") (pinfunction "g23_g23") (pintype "bidirectional"))
      (node (ref "J2") (pin "g26") (pinfunction "g26_g26") (pintype "bidirectional"))
      (node (ref "J2") (pin "g29") (pinfunction "g29_g29") (pintype "bidirectional"))
      (node (ref "J2") (pin "g32") (pinfunction "g32_g32") (pintype "bidirectional"))
      (node (ref "J2") (pin "g35") (pinfunction "g35_g35") (pintype "bidirectional"))
      (node (ref "J2") (pin "g38") (pinfunction "g38_g38") (pintype "bidirectional"))
      (node (ref "J2") (pin "g4") (pinfunction "g4_g4") (pintype "bidirectional"))
      (node (ref "J2") (pin "g40") (pinfunction "g40_g40") (pintype "bidirectional"))
      (node (ref "J2") (pin "g5") (pinfunction "g5_g5") (pintype "bidirectional"))
      (node (ref "J2") (pin "g8") (pinfunction "g8_g8") (pintype "bidirectional"))
      (node (ref "J2") (pin "h12") (pinfunction "h12_h12") (pintype "bidirectional"))
      (node (ref "J2") (pin "h15") (pinfunction "h15_h15") (pintype "bidirectional"))
      (node (ref "J2") (pin "h18") (pinfunction "h18_h18") (pintype "bidirectional"))
      (node (ref "J2") (pin "h21") (pinfunction "h21_h21") (pintype "bidirectional"))
      (node (ref "J2") (pin "h24") (pinfunction "h24_h24") (pintype "bidirectional"))
      (node (ref "J2") (pin "h27") (pinfunction "h27_h27") (pintype "bidirectional"))
      (node (ref "J2") (pin "h3") (pinfunction "h3_h3") (pintype "bidirectional"))
      (node (ref "J2") (pin "h30") (pinfunction "h30_h30") (pintype "bidirectional"))
      (node (ref "J2") (pin "h33") (pinfunction "h33_h33") (pintype "bidirectional"))
      (node (ref "J2") (pin "h36") (pinfunction "h36_h36") (pintype "bidirectional"))
      (node (ref "J2") (pin "h39") (pinfunction "h39_h39") (pintype "bidirectional"))
      (node (ref "J2") (pin "h6") (pinfunction "h6_h6") (pintype "bidirectional"))
      (node (ref "J2") (pin "h9") (pinfunction "h9_h9") (pintype "bidirectional"))
      (node (ref "J3") (pin "c1") (pinfunction "c1_c1") (pintype "bidirectional"))
      (node (ref "J3") (pin "c12") (pinfunction "c12_c12") (pintype "bidirectional"))
      (node (ref "J3") (pin "c13") (pinfunction "c13_c13") (pintype "bidirectional"))
      (node (ref "J3") (pin "c16") (pinfunction "c16_c16") (pintype "bidirectional"))
      (node (ref "J3") (pin "c17") (pinfunction "c17_c17") (pintype "bidirectional"))
      (node (ref "J3") (pin "c20") (pinfunction "c20_c20") (pintype "bidirectional"))
      (node (ref "J3") (pin "c21") (pinfunction "c21_c21") (pintype "bidirectional"))
      (node (ref "J3") (pin "c24") (pinfunction "c24_c24") (pintype "bidirectional"))
      (node (ref "J3") (pin "c25") (pinfunction "c25_c25") (pintype "bidirectional"))
      (node (ref "J3") (pin "c28") (pinfunction "c28_c28") (pintype "bidirectional"))
      (node (ref "J3") (pin "c29") (pinfunction "c29_c29") (pintype "bidirectional"))
      (node (ref "J3") (pin "c32") (pinfunction "c32_c32") (pintype "bidirectional"))
      (node (ref "J3") (pin "c33") (pinfunction "c33_c33") (pintype "bidirectional"))
      (node (ref "J3") (pin "c36") (pinfunction "c36_c36") (pintype "bidirectional"))
      (node (ref "J3") (pin "c38") (pinfunction "c38_c38") (pintype "bidirectional"))
      (node (ref "J3") (pin "c4") (pinfunction "c4_c4") (pintype "bidirectional"))
      (node (ref "J3") (pin "c40") (pinfunction "c40_c40") (pintype "bidirectional"))
      (node (ref "J3") (pin "c5") (pinfunction "c5_c5") (pintype "bidirectional"))
      (node (ref "J3") (pin "c8") (pinfunction "c8_c8") (pintype "bidirectional"))
      (node (ref "J3") (pin "c9") (pinfunction "c9_c9") (pintype "bidirectional"))
      (node (ref "J3") (pin "d10") (pinfunction "d10_d10") (pintype "bidirectional"))
      (node (ref "J3") (pin "d13") (pinfunction "d13_d13") (pintype "bidirectional"))
      (node (ref "J3") (pin "d16") (pinfunction "d16_d16") (pintype "bidirectional"))
      (node (ref "J3") (pin "d19") (pinfunction "d19_d19") (pintype "bidirectional"))
      (node (ref "J3") (pin "d2") (pinfunction "d2_d2") (pintype "bidirectional"))
      (node (ref "J3") (pin "d22") (pinfunction "d22_d22") (pintype "bidirectional"))
      (node (ref "J3") (pin "d25") (pinfunction "d25_d25") (pintype "bidirectional"))
      (node (ref "J3") (pin "d28") (pinfunction "d28_d28") (pintype "bidirectional"))
      (node (ref "J3") (pin "d3") (pinfunction "d3_d3") (pintype "bidirectional"))
      (node (ref "J3") (pin "d35") (pinfunction "d35_d35") (pintype "bidirectional"))
      (node (ref "J3") (pin "d37") (pinfunction "d37_d37") (pintype "bidirectional"))
      (node (ref "J3") (pin "d39") (pinfunction "d39_d39") (pintype "bidirectional"))
      (node (ref "J3") (pin "d6") (pinfunction "d6_d6") (pintype "bidirectional"))
      (node (ref "J3") (pin "d7") (pinfunction "d7_d7") (pintype "bidirectional"))
      (node (ref "J3") (pin "g1") (pinfunction "g1_g1") (pintype "bidirectional"))
      (node (ref "J3") (pin "g11") (pinfunction "g11_g11") (pintype "bidirectional"))
      (node (ref "J3") (pin "g14") (pinfunction "g14_g14") (pintype "bidirectional"))
      (node (ref "J3") (pin "g17") (pinfunction "g17_g17") (pintype "bidirectional"))
      (node (ref "J3") (pin "g20") (pinfunction "g20_g20") (pintype "bidirectional"))
      (node (ref "J3") (pin "g23") (pinfunction "g23_g23") (pintype "bidirectional"))
      (node (ref "J3") (pin "g26") (pinfunction "g26_g26") (pintype "bidirectional"))
      (node (ref "J3") (pin "g29") (pinfunction "g29_g29") (pintype "bidirectional"))
      (node (ref "J3") (pin "g32") (pinfunction "g32_g32") (pintype "bidirectional"))
      (node (ref "J3") (pin "g35") (pinfunction "g35_g35") (pintype "bidirectional"))
      (node (ref "J3") (pin "g38") (pinfunction "g38_g38") (pintype "bidirectional"))
      (node (ref "J3") (pin "g4") (pinfunction "g4_g4") (pintype "bidirectional"))
      (node (ref "J3") (pin "g40") (pinfunction "g40_g40") (pintype "bidirectional"))
      (node (ref "J3") (pin "g5") (pinfunction "g5_g5") (pintype "bidirectional"))
      (node (ref "J3") (pin "g8") (pinfunction "g8_g8") (pintype "bidirectional"))
      (node (ref "J3") (pin "h12") (pinfunction "h12_h12") (pintype "bidirectional"))
      (node (ref "J3") (pin "h15") (pinfunction "h15_h15") (pintype "bidirectional"))
      (node (ref "J3") (pin "h18") (pinfunction "h18_h18") (pintype "bidirectional"))
      (node (ref "J3") (pin "h21") (pinfunction "h21_h21") (pintype "bidirectional"))
      (node (ref "J3") (pin "h24") (pinfunction "h24_h24") (pintype "bidirectional"))
      (node (ref "J3") (pin "h27") (pinfunction "h27_h27") (pintype "bidirectional"))
      (node (ref "J3") (pin "h3") (pinfunction "h3_h3") (pintype "bidirectional"))
      (node (ref "J3") (pin "h30") (pinfunction "h30_h30") (pintype "bidirectional"))
      (node (ref "J3") (pin "h33") (pinfunction "h33_h33") (pintype "bidirectional"))
      (node (ref "J3") (pin "h36") (pinfunction "h36_h36") (pintype "bidirectional"))
      (node (ref "J3") (pin "h39") (pinfunction "h39_h39") (pintype "bidirectional"))
      (node (ref "J3") (pin "h6") (pinfunction "h6_h6") (pintype "bidirectional"))
      (node (ref "J3") (pin "h9") (pinfunction "h9_h9") (pintype "bidirectional"))
    )
    (net (code "182") (name "Net-(J3-Padc34)") (class "Default")
      (node (ref "J3") (pin "c34") (pinfunction "c34_c34") (pintype "bidirectional"))
      (node (ref "R276") (pin "2") (pinfunction "2_2") (pintype "passive"))
    )
    (net (code "183") (name "P2V5_FMC") (class "Default")
      (node (ref "C280") (pin "2") (pinfunction "2_2") (pintype "passive"))
      (node (ref "C291") (pin "2") (pinfunction "2_2") (pintype "passive"))
      (node (ref "C82") (pin "2") (pinfunction "2_2") (pintype "passive"))
      (node (ref "C83") (pin "2") (pinfunction "2_2") (pintype "passive"))
      (node (ref "C84") (pin "2") (pinfunction "2_2") (pintype "passive"))
      (node (ref "C85") (pin "2") (pinfunction "2_2") (pintype "passive"))
      (node (ref "C86") (pin "2") (pinfunction "2_2") (pintype "passive"))
      (node (ref "C87") (pin "2") (pinfunction "2_2") (pintype "passive"))
      (node (ref "J2") (pin "g39") (pinfunction "g39_g39") (pintype "bidirectional"))
      (node (ref "J2") (pin "h40") (pinfunction "h40_h40") (pintype "bidirectional"))
      (node (ref "J3") (pin "g39") (pinfunction "g39_g39") (pintype "bidirectional"))
      (node (ref "J3") (pin "h40") (pinfunction "h40_h40") (pintype "bidirectional"))
    )
    (net (code "184") (name "P3V3") (class "Default")
      (node (ref "C431") (pin "2") (pinfunction "2_2") (pintype "passive"))
      (node (ref "C76") (pin "2") (pinfunction "2_2") (pintype "passive"))
      (node (ref "J2") (pin "d32") (pinfunction "d32_d32") (pintype "bidirectional"))
      (node (ref "J3") (pin "d32") (pinfunction "d32_d32") (pintype "bidirectional"))
      (node (ref "R233") (pin "2") (pinfunction "2_2") (pintype "passive"))
      (node (ref "R276") (pin "1") (pinfunction "1_1") (pintype "passive"))
      (node (ref "R277") (pin "2") (pinfunction "2_2") (pintype "passive"))
      (node (ref "R29") (pin "1") (pinfunction "1_1") (pintype "passive"))
      (node (ref "R30") (pin "1") (pinfunction "1_1") (pintype "passive"))
      (node (ref "R51") (pin "1") (pinfunction "1_1") (pintype "passive"))
      (node (ref "R84") (pin "1") (pinfunction "1_1") (pintype "passive"))
    )
    (net (code "185") (name "P3V3_FMC1") (class "Default")
      (node (ref "C239") (pin "2") (pinfunction "2_2") (pintype "passive"))
      (node (ref "C56") (pin "2") (pinfunction "2_2") (pintype "passive"))
      (node (ref "C65") (pin "2") (pinfunction "2_2") (pintype "passive"))
      (node (ref "C70") (pin "2") (pinfunction "2_2") (pintype "passive"))
      (node (ref "J2") (pin "c39") (pinfunction "c39_c39") (pintype "bidirectional"))
      (node (ref "J2") (pin "d36") (pinfunction "d36_d36") (pintype "bidirectional"))
      (node (ref "J2") (pin "d38") (pinfunction "d38_d38") (pintype "bidirectional"))
      (node (ref "J2") (pin "d40") (pinfunction "d40_d40") (pintype "bidirectional"))
    )
    (net (code "186") (name "P3V3_FMC2") (class "Default")
      (node (ref "C255") (pin "2") (pinfunction "2_2") (pintype "passive"))
      (node (ref "C63") (pin "2") (pinfunction "2_2") (pintype "passive"))
      (node (ref "C69") (pin "2") (pinfunction "2_2") (pintype "passive"))
      (node (ref "C73") (pin "2") (pinfunction "2_2") (pintype "passive"))
      (node (ref "J3") (pin "c39") (pinfunction "c39_c39") (pintype "bidirectional"))
      (node (ref "J3") (pin "d36") (pinfunction "d36_d36") (pintype "bidirectional"))
      (node (ref "J3") (pin "d38") (pinfunction "d38_d38") (pintype "bidirectional"))
      (node (ref "J3") (pin "d40") (pinfunction "d40_d40") (pintype "bidirectional"))
    )
    (net (code "187") (name "P12V_FMC") (class "Default")
      (node (ref "C256") (pin "2") (pinfunction "2_2") (pintype "passive"))
      (node (ref "C263") (pin "2") (pinfunction "2_2") (pintype "passive"))
      (node (ref "C301") (pin "1") (pinfunction "1_1") (pintype "passive"))
      (node (ref "C308") (pin "1") (pinfunction "1_1") (pintype "passive"))
      (node (ref "J2") (pin "c35") (pinfunction "c35_c35") (pintype "bidirectional"))
      (node (ref "J2") (pin "c37") (pinfunction "c37_c37") (pintype "bidirectional"))
      (node (ref "J3") (pin "c35") (pinfunction "c35_c35") (pintype "bidirectional"))
      (node (ref "J3") (pin "c37") (pinfunction "c37_c37") (pintype "bidirectional"))
    )
  )
)
